# Temperature_Sense.net
KiCad netlist of a schematic drawn in Altium Designer
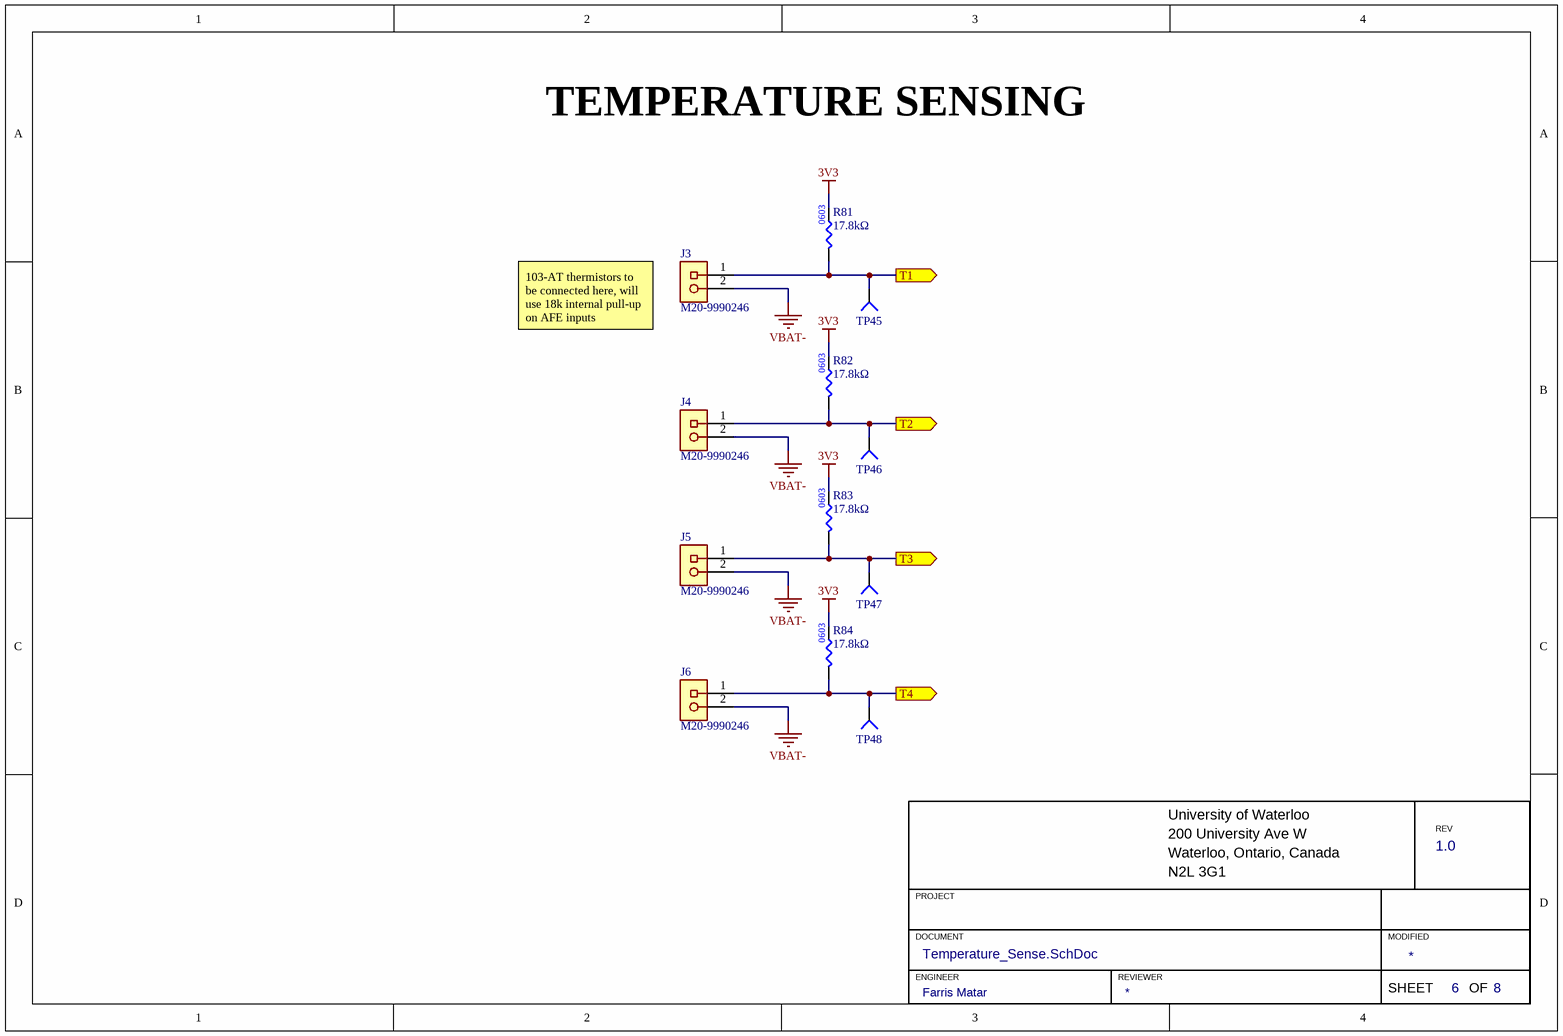
[diagram p0: Temperature_Sense.SchDoc]

(export (version "E")
  (design (tool "Eeschema 10.0.6"))
  (components
    (comp (ref "J3")
      (value "HEADER 2x1")
      (footprint "HDR1X2")
      (description "HEADER 2X1")
      (fields (field (name "MANUFACTURER PART NUMBER 1") "M20-9990246"))
      (libsource (lib "Personal_Schematic_Library_2022") (part "HEADER 2x1"))
    )
    (comp (ref "J4")
      (value "HEADER 2x1")
      (footprint "HDR1X2")
      (description "HEADER 2X1")
      (fields (field (name "MANUFACTURER PART NUMBER 1") "M20-9990246"))
      (libsource (lib "Personal_Schematic_Library_2022") (part "HEADER 2x1"))
    )
    (comp (ref "J5")
      (value "HEADER 2x1")
      (footprint "HDR1X2")
      (description "HEADER 2X1")
      (fields (field (name "MANUFACTURER PART NUMBER 1") "M20-9990246"))
      (libsource (lib "Personal_Schematic_Library_2022") (part "HEADER 2x1"))
    )
    (comp (ref "J6")
      (value "HEADER 2x1")
      (footprint "HDR1X2")
      (description "HEADER 2X1")
      (fields (field (name "MANUFACTURER PART NUMBER 1") "M20-9990246"))
      (libsource (lib "Personal_Schematic_Library_2022") (part "HEADER 2x1"))
    )
    (comp (ref "R81")
      (value "17.8kΩ")
      (footprint "RES0603")
      (description "RES 17.8K OHM 1% 1/10W 0603")
      (fields (field (name "Comment") "RES_17.8kΩ_0603_1%"))
      (libsource (lib "Personal_Schematic_Library_2022") (part "RES_17.8kΩ_0603_1%"))
    )
    (comp (ref "R82")
      (value "17.8kΩ")
      (footprint "RES0603")
      (description "RES 17.8K OHM 1% 1/10W 0603")
      (fields (field (name "Comment") "RES_17.8kΩ_0603_1%"))
      (libsource (lib "Personal_Schematic_Library_2022") (part "RES_17.8kΩ_0603_1%"))
    )
    (comp (ref "R83")
      (value "17.8kΩ")
      (footprint "RES0603")
      (description "RES 17.8K OHM 1% 1/10W 0603")
      (fields (field (name "Comment") "RES_17.8kΩ_0603_1%"))
      (libsource (lib "Personal_Schematic_Library_2022") (part "RES_17.8kΩ_0603_1%"))
    )
    (comp (ref "R84")
      (value "17.8kΩ")
      (footprint "RES0603")
      (description "RES 17.8K OHM 1% 1/10W 0603")
      (fields (field (name "Comment") "RES_17.8kΩ_0603_1%"))
      (libsource (lib "Personal_Schematic_Library_2022") (part "RES_17.8kΩ_0603_1%"))
    )
    (comp (ref "TP45")
      (value "TESTPOINT_1MM_CIRCLE")
      (footprint "TESTPOINT_CIRCLE_1MM")
      (description "TESTPOINT 1MM CIRCLE")
      (libsource (lib "Personal_Schematic_Library_2022") (part "TESTPOINT_1MM_CIRCLE"))
    )
    (comp (ref "TP46")
      (value "TESTPOINT_1MM_CIRCLE")
      (footprint "TESTPOINT_CIRCLE_1MM")
      (description "TESTPOINT 1MM CIRCLE")
      (libsource (lib "Personal_Schematic_Library_2022") (part "TESTPOINT_1MM_CIRCLE"))
    )
    (comp (ref "TP47")
      (value "TESTPOINT_1MM_CIRCLE")
      (footprint "TESTPOINT_CIRCLE_1MM")
      (description "TESTPOINT 1MM CIRCLE")
      (libsource (lib "Personal_Schematic_Library_2022") (part "TESTPOINT_1MM_CIRCLE"))
    )
    (comp (ref "TP48")
      (value "TESTPOINT_1MM_CIRCLE")
      (footprint "TESTPOINT_CIRCLE_1MM")
      (description "TESTPOINT 1MM CIRCLE")
      (libsource (lib "Personal_Schematic_Library_2022") (part "TESTPOINT_1MM_CIRCLE"))
    )
  )
  (nets
    (net (code "1") (name "/T1") (class "Default")
      (node (ref "J3") (pin "1") (pinfunction "VCC_1") (pintype "passive"))
      (node (ref "R81") (pin "1") (pinfunction "1_1") (pintype "passive"))
      (node (ref "TP45") (pin "1") (pinfunction "=value_1") (pintype "passive"))
    )
    (net (code "2") (name "/T2") (class "Default")
      (node (ref "J4") (pin "1") (pinfunction "VCC_1") (pintype "passive"))
      (node (ref "R82") (pin "1") (pinfunction "1_1") (pintype "passive"))
      (node (ref "TP46") (pin "1") (pinfunction "=value_1") (pintype "passive"))
    )
    (net (code "3") (name "/T3") (class "Default")
      (node (ref "J5") (pin "1") (pinfunction "VCC_1") (pintype "passive"))
      (node (ref "R83") (pin "1") (pinfunction "1_1") (pintype "passive"))
      (node (ref "TP47") (pin "1") (pinfunction "=value_1") (pintype "passive"))
    )
    (net (code "4") (name "/T4") (class "Default")
      (node (ref "J6") (pin "1") (pinfunction "VCC_1") (pintype "passive"))
      (node (ref "R84") (pin "1") (pinfunction "1_1") (pintype "passive"))
      (node (ref "TP48") (pin "1") (pinfunction "=value_1") (pintype "passive"))
    )
    (net (code "5") (name "3V3") (class "Default")
      (node (ref "R81") (pin "2") (pinfunction "2_2") (pintype "passive"))
      (node (ref "R82") (pin "2") (pinfunction "2_2") (pintype "passive"))
      (node (ref "R83") (pin "2") (pinfunction "2_2") (pintype "passive"))
      (node (ref "R84") (pin "2") (pinfunction "2_2") (pintype "passive"))
    )
    (net (code "6") (name "VBAT-") (class "Default")
      (node (ref "J3") (pin "2") (pinfunction "2_2") (pintype "passive"))
      (node (ref "J4") (pin "2") (pinfunction "2_2") (pintype "passive"))
      (node (ref "J5") (pin "2") (pinfunction "2_2") (pintype "passive"))
      (node (ref "J6") (pin "2") (pinfunction "2_2") (pintype "passive"))
    )
  )
)
